# Rocketry_circuit.net
KiCad netlist of a schematic drawn in EAGLE
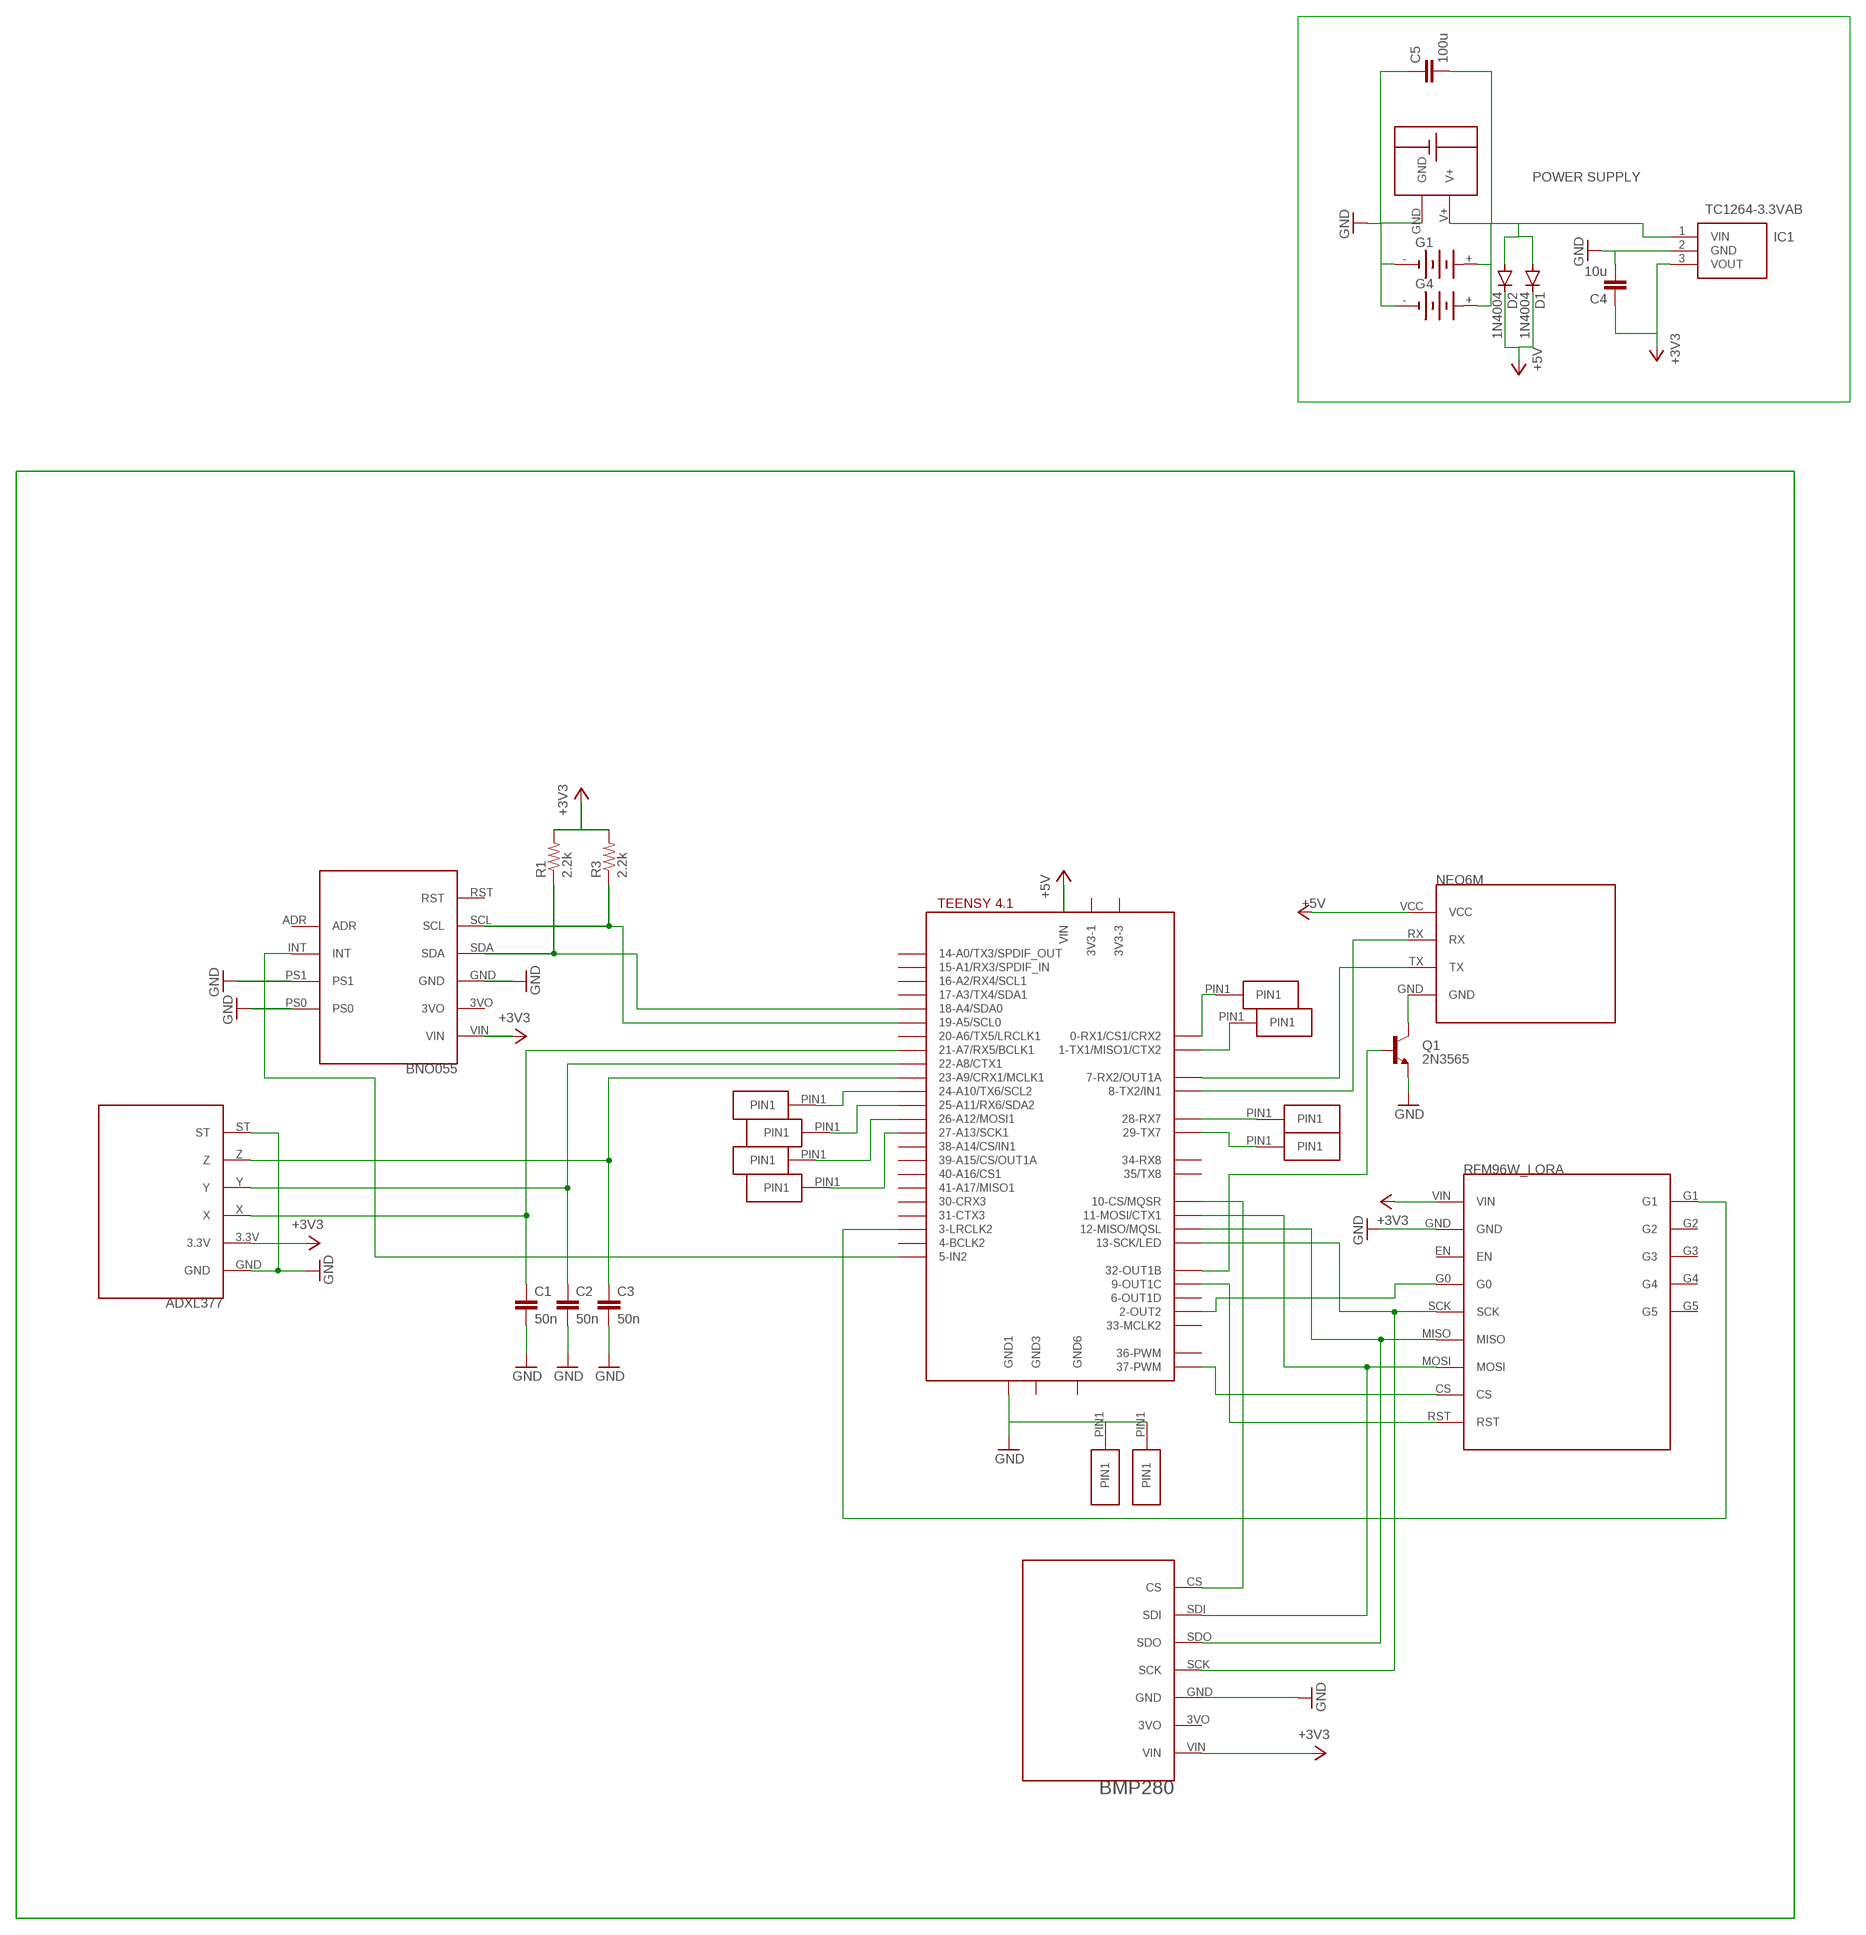
[diagram p0: schematic, sheet 1]

(export (version "E")
  (design (tool "Eeschema 10.0.6"))
  (components
    (comp (ref "BRKOUT1")
      (value "BNO055")
      (footprint "eagle-import:BNO055")
      (libsource (lib "eagle-import") (part "BNO055"))
    )
    (comp (ref "C1")
      (value "50n")
      (footprint "eagle-import:C2.5-3")
      (libsource (lib "eagle-import") (part "C2,5-3"))
    )
    (comp (ref "C2")
      (value "50n")
      (footprint "eagle-import:C2.5-3")
      (libsource (lib "eagle-import") (part "C2,5-3"))
    )
    (comp (ref "C3")
      (value "50n")
      (footprint "eagle-import:C2.5-3")
      (libsource (lib "eagle-import") (part "C2,5-3"))
    )
    (comp (ref "C4")
      (value "10u")
      (footprint "eagle-import:C2.5-3")
      (libsource (lib "eagle-import") (part "C2,5-3"))
    )
    (comp (ref "C5")
      (value "100u")
      (footprint "eagle-import:C2.5-3")
      (libsource (lib "eagle-import") (part "C2,5-3"))
    )
    (comp (ref "D1")
      (value "1N4004")
      (footprint "eagle-import:DO41-10")
      (libsource (lib "eagle-import") (part "1N4004"))
    )
    (comp (ref "D2")
      (value "1N4004")
      (footprint "eagle-import:DO41-10")
      (libsource (lib "eagle-import") (part "1N4004"))
    )
    (comp (ref "G1")
      (value "3V11R")
      (footprint "eagle-import:3V11R")
      (libsource (lib "eagle-import") (part "3V11R"))
    )
    (comp (ref "G4")
      (value "3V11R")
      (footprint "eagle-import:3V11R")
      (libsource (lib "eagle-import") (part "3V11R"))
    )
    (comp (ref "IC1")
      (value "TC1264-3.3VAB")
      (footprint "eagle-import:TO254P483X988X2222-3P")
      (fields (field (name "MOUSER_PART_NUMBER") "579-TC1264-3.3VAB"))
      (libsource (lib "eagle-import") (part "TC1264-3.3VAB"))
    )
    (comp (ref "Q1")
      (value "2N3565")
      (footprint "eagle-import:TO92")
      (libsource (lib "eagle-import") (part "2N3565"))
    )
    (comp (ref "R1")
      (value "2.2k")
      (footprint "eagle-import:0207_5V")
      (libsource (lib "eagle-import") (part "R-US_0207/5V"))
    )
    (comp (ref "R3")
      (value "2.2k")
      (footprint "eagle-import:0207_5V")
      (libsource (lib "eagle-import") (part "R-US_0207/5V"))
    )
    (comp (ref "U$1")
      (value "TEENSY41")
      (footprint "eagle-import:TEENSY41")
      (libsource (lib "eagle-import") (part "TEENSY41"))
    )
    (comp (ref "U$2")
      (value "BMP280")
      (footprint "eagle-import:BMP280")
      (libsource (lib "eagle-import") (part "BMP280"))
    )
    (comp (ref "U$3")
      (value "ADXL377")
      (footprint "eagle-import:ADXL377")
      (libsource (lib "eagle-import") (part "ADXL377"))
    )
    (comp (ref "U$4")
      (value "NEO6M")
      (footprint "eagle-import:NEO6M")
      (libsource (lib "eagle-import") (part "NEO6M"))
    )
    (comp (ref "U$5")
      (value "RFM96W")
      (footprint "eagle-import:RFM96W")
      (libsource (lib "eagle-import") (part "RFM96W"))
    )
    (comp (ref "U$6")
      (value "1PINOUT")
      (footprint "eagle-import:1PINOUT")
      (libsource (lib "eagle-import") (part "1PINOUT"))
    )
    (comp (ref "U$7")
      (value "1PINOUT")
      (footprint "eagle-import:1PINOUT")
      (libsource (lib "eagle-import") (part "1PINOUT"))
    )
    (comp (ref "U$8")
      (value "1PINOUT")
      (footprint "eagle-import:1PINOUT")
      (libsource (lib "eagle-import") (part "1PINOUT"))
    )
    (comp (ref "U$9")
      (value "1PINOUT")
      (footprint "eagle-import:1PINOUT")
      (libsource (lib "eagle-import") (part "1PINOUT"))
    )
    (comp (ref "U$10")
      (value "1PINOUT")
      (footprint "eagle-import:1PINOUT")
      (libsource (lib "eagle-import") (part "1PINOUT"))
    )
    (comp (ref "U$11")
      (value "1PINOUT")
      (footprint "eagle-import:1PINOUT")
      (libsource (lib "eagle-import") (part "1PINOUT"))
    )
    (comp (ref "U$12")
      (value "SMALL_SCREW_TERMINAL")
      (footprint "eagle-import:SMALL_SCREW_TERMINAL")
      (libsource (lib "eagle-import") (part "SMALL_SCREW_TERMINAL"))
    )
    (comp (ref "U$13")
      (value "1PINOUT")
      (footprint "eagle-import:1PINOUT")
      (libsource (lib "eagle-import") (part "1PINOUT"))
    )
    (comp (ref "U$14")
      (value "1PINOUT")
      (footprint "eagle-import:1PINOUT")
      (libsource (lib "eagle-import") (part "1PINOUT"))
    )
    (comp (ref "U$15")
      (value "1PINOUT")
      (footprint "eagle-import:1PINOUT")
      (libsource (lib "eagle-import") (part "1PINOUT"))
    )
    (comp (ref "U$16")
      (value "1PINOUT")
      (footprint "eagle-import:1PINOUT")
      (libsource (lib "eagle-import") (part "1PINOUT"))
    )
  )
  (nets
    (net (code "1") (name "+3V3") (class "Default")
      (node (ref "BRKOUT1") (pin "VIN") (pinfunction "VIN_VIN") (pintype "power_in"))
      (node (ref "C4") (pin "1") (pinfunction "1_1") (pintype "passive"))
      (node (ref "IC1") (pin "3") (pinfunction "VOUT_3") (pintype "bidirectional"))
      (node (ref "R1") (pin "2") (pinfunction "2_2") (pintype "passive"))
      (node (ref "R3") (pin "2") (pinfunction "2_2") (pintype "passive"))
      (node (ref "U$2") (pin "VIN") (pinfunction "VIN_VIN") (pintype "bidirectional"))
      (node (ref "U$3") (pin "3.3V") (pinfunction "3.3V_3.3V") (pintype "bidirectional"))
      (node (ref "U$5") (pin "VIN") (pinfunction "VIN_VIN") (pintype "bidirectional"))
    )
    (net (code "2") (name "+5V") (class "Default")
      (node (ref "D1") (pin "C") (pinfunction "C_C") (pintype "passive"))
      (node (ref "D2") (pin "C") (pinfunction "C_C") (pintype "passive"))
      (node (ref "U$1") (pin "VIN") (pinfunction "VIN_VIN") (pintype "bidirectional"))
      (node (ref "U$4") (pin "VCC") (pinfunction "VCC_VCC") (pintype "bidirectional"))
    )
    (net (code "3") (name "/3VO") (class "Default")
      (node (ref "BRKOUT1") (pin "3VO") (pinfunction "3VO_3VO") (pintype "power_in"))
    )
    (net (code "4") (name "GND") (class "Default")
      (node (ref "BRKOUT1") (pin "GND") (pinfunction "GND_GND") (pintype "power_in"))
      (node (ref "BRKOUT1") (pin "PS0") (pinfunction "PS0_PS0") (pintype "bidirectional"))
      (node (ref "BRKOUT1") (pin "PS1") (pinfunction "PS1_PS1") (pintype "bidirectional"))
      (node (ref "C1") (pin "2") (pinfunction "2_2") (pintype "passive"))
      (node (ref "C2") (pin "2") (pinfunction "2_2") (pintype "passive"))
      (node (ref "C3") (pin "2") (pinfunction "2_2") (pintype "passive"))
      (node (ref "C4") (pin "2") (pinfunction "2_2") (pintype "passive"))
      (node (ref "C5") (pin "1") (pinfunction "1_1") (pintype "passive"))
      (node (ref "G1") (pin "-") (pinfunction "-_-") (pintype "passive"))
      (node (ref "G4") (pin "-") (pinfunction "-_-") (pintype "passive"))
      (node (ref "IC1") (pin "2") (pinfunction "GND_2") (pintype "bidirectional"))
      (node (ref "Q1") (pin "3") (pinfunction "E_3") (pintype "passive"))
      (node (ref "U$1") (pin "GND1") (pinfunction "GND1_GND1") (pintype "bidirectional"))
      (node (ref "U$10") (pin "PIN1") (pinfunction "PIN1_PIN1") (pintype "bidirectional"))
      (node (ref "U$11") (pin "PIN1") (pinfunction "PIN1_PIN1") (pintype "bidirectional"))
      (node (ref "U$12") (pin "GND") (pinfunction "GND_GND") (pintype "bidirectional"))
      (node (ref "U$2") (pin "GND") (pinfunction "GND_GND") (pintype "bidirectional"))
      (node (ref "U$3") (pin "GND") (pinfunction "GND_GND") (pintype "bidirectional"))
      (node (ref "U$3") (pin "ST") (pinfunction "ST_ST") (pintype "bidirectional"))
      (node (ref "U$5") (pin "GND") (pinfunction "GND_GND") (pintype "bidirectional"))
    )
    (net (code "5") (name "Net-(BRKOUT1-PadINT)") (class "Default")
      (node (ref "BRKOUT1") (pin "INT") (pinfunction "INT_INT") (pintype "bidirectional"))
      (node (ref "U$1") (pin "5-IN2") (pinfunction "5-IN2_5-IN2") (pintype "bidirectional"))
    )
    (net (code "6") (name "Net-(BRKOUT1-PadSCL)") (class "Default")
      (node (ref "BRKOUT1") (pin "SCL") (pinfunction "SCL_SCL") (pintype "bidirectional"))
      (node (ref "R3") (pin "1") (pinfunction "1_1") (pintype "passive"))
      (node (ref "U$1") (pin "19-A5/SCL0") (pinfunction "19-A5/SCL0_19-A5/SCL0") (pintype "bidirectional"))
    )
    (net (code "7") (name "Net-(BRKOUT1-PadSDA)") (class "Default")
      (node (ref "BRKOUT1") (pin "SDA") (pinfunction "SDA_SDA") (pintype "bidirectional"))
      (node (ref "R1") (pin "1") (pinfunction "1_1") (pintype "passive"))
      (node (ref "U$1") (pin "18-A4/SDA0") (pinfunction "18-A4/SDA0_18-A4/SDA0") (pintype "bidirectional"))
    )
    (net (code "8") (name "Net-(C1-Pad1)") (class "Default")
      (node (ref "C1") (pin "1") (pinfunction "1_1") (pintype "passive"))
      (node (ref "U$1") (pin "21-A7/RX5/BCLK1") (pinfunction "21-A7/RX5/BCLK1_21-A7/RX5/BCLK1") (pintype "bidirectional"))
      (node (ref "U$3") (pin "X") (pinfunction "X_X") (pintype "bidirectional"))
    )
    (net (code "9") (name "Net-(C2-Pad1)") (class "Default")
      (node (ref "C2") (pin "1") (pinfunction "1_1") (pintype "passive"))
      (node (ref "U$1") (pin "22-A8/CTX1") (pinfunction "22-A8/CTX1_22-A8/CTX1") (pintype "bidirectional"))
      (node (ref "U$3") (pin "Y") (pinfunction "Y_Y") (pintype "bidirectional"))
    )
    (net (code "10") (name "Net-(C3-Pad1)") (class "Default")
      (node (ref "C3") (pin "1") (pinfunction "1_1") (pintype "passive"))
      (node (ref "U$1") (pin "23-A9/CRX1/MCLK1") (pinfunction "23-A9/CRX1/MCLK1_23-A9/CRX1/MCLK1") (pintype "bidirectional"))
      (node (ref "U$3") (pin "Z") (pinfunction "Z_Z") (pintype "bidirectional"))
    )
    (net (code "11") (name "Net-(IC1-VIN)") (class "Default")
      (node (ref "C5") (pin "2") (pinfunction "2_2") (pintype "passive"))
      (node (ref "D1") (pin "A") (pinfunction "A_A") (pintype "passive"))
      (node (ref "D2") (pin "A") (pinfunction "A_A") (pintype "passive"))
      (node (ref "G1") (pin "+") (pinfunction "+_+") (pintype "passive"))
      (node (ref "G4") (pin "+") (pinfunction "+_+") (pintype "passive"))
      (node (ref "IC1") (pin "1") (pinfunction "VIN_1") (pintype "bidirectional"))
      (node (ref "U$12") (pin "V+") (pinfunction "V+_V+") (pintype "bidirectional"))
    )
    (net (code "12") (name "Net-(Q1-B)") (class "Default")
      (node (ref "Q1") (pin "2") (pinfunction "B_2") (pintype "passive"))
      (node (ref "U$1") (pin "32-OUT1B") (pinfunction "32-OUT1B_32-OUT1B") (pintype "bidirectional"))
    )
    (net (code "13") (name "Net-(Q1-C)") (class "Default")
      (node (ref "Q1") (pin "1") (pinfunction "C_1") (pintype "passive"))
      (node (ref "U$4") (pin "GND") (pinfunction "GND_GND") (pintype "bidirectional"))
    )
    (net (code "14") (name "Net-(U$1-8-TX2{slash}IN1)") (class "Default")
      (node (ref "U$1") (pin "8-TX2/IN2") (pinfunction "8-TX2/IN1_8-TX2/IN2") (pintype "bidirectional"))
      (node (ref "U$4") (pin "RX") (pinfunction "RX_RX") (pintype "bidirectional"))
    )
    (net (code "15") (name "Net-(U$1-10-CS{slash}MQSR)") (class "Default")
      (node (ref "U$1") (pin "10-CS\\MQSR") (pinfunction "10-CS/MQSR_10-CS\\MQSR") (pintype "bidirectional"))
      (node (ref "U$2") (pin "CS") (pinfunction "CS_CS") (pintype "bidirectional"))
    )
    (net (code "16") (name "Net-(U$1-Pad0-RX1{slash}CS1{slash}CRX2)") (class "Default")
      (node (ref "U$1") (pin "0-RX1/CS1/CRX2") (pinfunction "0-RX1/CS1/CRX2_0-RX1/CS1/CRX2") (pintype "bidirectional"))
      (node (ref "U$15") (pin "PIN1") (pinfunction "PIN1_PIN1") (pintype "bidirectional"))
    )
    (net (code "17") (name "Net-(U$1-Pad1-TX1{slash}MISO1{slash}CTX2)") (class "Default")
      (node (ref "U$1") (pin "1-TX1/MISO1/CTX2") (pinfunction "1-TX1/MISO1/CTX2_1-TX1/MISO1/CTX2") (pintype "bidirectional"))
      (node (ref "U$16") (pin "PIN1") (pinfunction "PIN1_PIN1") (pintype "bidirectional"))
    )
    (net (code "18") (name "Net-(U$1-Pad2-OUT2)") (class "Default")
      (node (ref "U$1") (pin "2-OUT2") (pinfunction "2-OUT2_2-OUT2") (pintype "bidirectional"))
      (node (ref "U$5") (pin "G0") (pinfunction "G0_G0") (pintype "bidirectional"))
    )
    (net (code "19") (name "Net-(U$1-Pad3-LRCLK2)") (class "Default")
      (node (ref "U$1") (pin "3-LRCLK2") (pinfunction "3-LRCLK2_3-LRCLK2") (pintype "bidirectional"))
      (node (ref "U$5") (pin "G1") (pinfunction "G1_G1") (pintype "bidirectional"))
    )
    (net (code "20") (name "Net-(U$1-Pad7-RX2{slash}OUT1A)") (class "Default")
      (node (ref "U$1") (pin "7-RX2/OUT1A") (pinfunction "7-RX2/OUT1A_7-RX2/OUT1A") (pintype "bidirectional"))
      (node (ref "U$4") (pin "TX") (pinfunction "TX_TX") (pintype "bidirectional"))
    )
    (net (code "21") (name "Net-(U$1-Pad9-OUT1C)") (class "Default")
      (node (ref "U$1") (pin "9-OUT1C") (pinfunction "9-OUT1C_9-OUT1C") (pintype "bidirectional"))
      (node (ref "U$5") (pin "RST") (pinfunction "RST_RST") (pintype "bidirectional"))
    )
    (net (code "22") (name "Net-(U$1-Pad11-MOSI{slash}CTX1)") (class "Default")
      (node (ref "U$1") (pin "11-MOSI/CTX1") (pinfunction "11-MOSI/CTX1_11-MOSI/CTX1") (pintype "bidirectional"))
      (node (ref "U$2") (pin "SDI") (pinfunction "SDI_SDI") (pintype "bidirectional"))
      (node (ref "U$5") (pin "MOSI") (pinfunction "MOSI_MOSI") (pintype "bidirectional"))
    )
    (net (code "23") (name "Net-(U$1-Pad12-MISO{slash}MQSL)") (class "Default")
      (node (ref "U$1") (pin "12-MISO/MQSL") (pinfunction "12-MISO/MQSL_12-MISO/MQSL") (pintype "bidirectional"))
      (node (ref "U$2") (pin "SDO") (pinfunction "SDO_SDO") (pintype "bidirectional"))
      (node (ref "U$5") (pin "MISO") (pinfunction "MISO_MISO") (pintype "bidirectional"))
    )
    (net (code "24") (name "Net-(U$1-Pad13-SCK{slash}LED)") (class "Default")
      (node (ref "U$1") (pin "13-SCK/LED") (pinfunction "13-SCK/LED_13-SCK/LED") (pintype "bidirectional"))
      (node (ref "U$2") (pin "SCK") (pinfunction "SCK_SCK") (pintype "bidirectional"))
      (node (ref "U$5") (pin "SCK") (pinfunction "SCK_SCK") (pintype "bidirectional"))
    )
    (net (code "25") (name "Net-(U$1-Pad24-A10{slash}TX6{slash}SCL2)") (class "Default")
      (node (ref "U$1") (pin "24-A10/TX6/SCL2") (pinfunction "24-A10/TX6/SCL2_24-A10/TX6/SCL2") (pintype "bidirectional"))
      (node (ref "U$9") (pin "PIN1") (pinfunction "PIN1_PIN1") (pintype "bidirectional"))
    )
    (net (code "26") (name "Net-(U$1-Pad25-A11{slash}RX6{slash}SDA2)") (class "Default")
      (node (ref "U$1") (pin "25-A11/RX6/SDA2") (pinfunction "25-A11/RX6/SDA2_25-A11/RX6/SDA2") (pintype "bidirectional"))
      (node (ref "U$7") (pin "PIN1") (pinfunction "PIN1_PIN1") (pintype "bidirectional"))
    )
    (net (code "27") (name "Net-(U$1-Pad26-A12{slash}MOSI1)") (class "Default")
      (node (ref "U$1") (pin "26-A12/MOSI1") (pinfunction "26-A12/MOSI1_26-A12/MOSI1") (pintype "bidirectional"))
      (node (ref "U$13") (pin "PIN1") (pinfunction "PIN1_PIN1") (pintype "bidirectional"))
    )
    (net (code "28") (name "Net-(U$1-Pad27-A13{slash}SCK1)") (class "Default")
      (node (ref "U$1") (pin "27-A13/SCK1") (pinfunction "27-A13/SCK1_27-A13/SCK1") (pintype "bidirectional"))
      (node (ref "U$14") (pin "PIN1") (pinfunction "PIN1_PIN1") (pintype "bidirectional"))
    )
    (net (code "29") (name "Net-(U$1-Pad28-RX7)") (class "Default")
      (node (ref "U$1") (pin "28-RX7") (pinfunction "28-RX7_28-RX7") (pintype "bidirectional"))
      (node (ref "U$6") (pin "PIN1") (pinfunction "PIN1_PIN1") (pintype "bidirectional"))
    )
    (net (code "30") (name "Net-(U$1-Pad29-TX7)") (class "Default")
      (node (ref "U$1") (pin "29-TX7") (pinfunction "29-TX7_29-TX7") (pintype "bidirectional"))
      (node (ref "U$8") (pin "PIN1") (pinfunction "PIN1_PIN1") (pintype "bidirectional"))
    )
    (net (code "31") (name "Net-(U$1-Pad37-PWM)") (class "Default")
      (node (ref "U$1") (pin "37-PWM") (pinfunction "37-PWM_37-PWM") (pintype "bidirectional"))
      (node (ref "U$5") (pin "CS") (pinfunction "CS_CS") (pintype "bidirectional"))
    )
    (net (code "32") (name "unconnected-(BRKOUT1-PadADR)") (class "Default")
      (node (ref "BRKOUT1") (pin "ADR") (pinfunction "ADR_ADR") (pintype "bidirectional"))
    )
    (net (code "33") (name "unconnected-(BRKOUT1-PadRST)") (class "Default")
      (node (ref "BRKOUT1") (pin "RST") (pinfunction "RST_RST") (pintype "bidirectional"))
    )
    (net (code "34") (name "unconnected-(U$1-35{slash}TX8-Pad35-TX8)") (class "Default")
      (node (ref "U$1") (pin "35-TX8") (pinfunction "35/TX8_35-TX8") (pintype "bidirectional"))
    )
    (net (code "35") (name "unconnected-(U$1-Pad3V3-1)") (class "Default")
      (node (ref "U$1") (pin "3V3-1") (pinfunction "3V3-1_3V3-1") (pintype "bidirectional"))
    )
    (net (code "36") (name "unconnected-(U$1-Pad3V3-3)") (class "Default")
      (node (ref "U$1") (pin "3V3-3") (pinfunction "3V3-3_3V3-3") (pintype "bidirectional"))
    )
    (net (code "37") (name "unconnected-(U$1-Pad4-BCLK2)") (class "Default")
      (node (ref "U$1") (pin "4-BCLK2") (pinfunction "4-BCLK2_4-BCLK2") (pintype "bidirectional"))
    )
    (net (code "38") (name "unconnected-(U$1-Pad6-OUT1D)") (class "Default")
      (node (ref "U$1") (pin "6-OUT1D") (pinfunction "6-OUT1D_6-OUT1D") (pintype "bidirectional"))
    )
    (net (code "39") (name "unconnected-(U$1-Pad14-A0{slash}TX3{slash}SPDIF_OUT)") (class "Default")
      (node (ref "U$1") (pin "14-A0/TX3/SPDIF_OUT") (pinfunction "14-A0/TX3/SPDIF_OUT_14-A0/TX3/SPDIF_OUT") (pintype "bidirectional"))
    )
    (net (code "40") (name "unconnected-(U$1-Pad15-A1{slash}RX3{slash}SPDIF_IN)") (class "Default")
      (node (ref "U$1") (pin "15-A1/RX3/SPDIF_IN") (pinfunction "15-A1/RX3/SPDIF_IN_15-A1/RX3/SPDIF_IN") (pintype "bidirectional"))
    )
    (net (code "41") (name "unconnected-(U$1-Pad16-A2{slash}RX4{slash}SCL1)") (class "Default")
      (node (ref "U$1") (pin "16-A2/RX4/SCL1") (pinfunction "16-A2/RX4/SCL1_16-A2/RX4/SCL1") (pintype "bidirectional"))
    )
    (net (code "42") (name "unconnected-(U$1-Pad17-A3{slash}TX4{slash}SDA1)") (class "Default")
      (node (ref "U$1") (pin "17-A3/TX4/SDA1") (pinfunction "17-A3/TX4/SDA1_17-A3/TX4/SDA1") (pintype "bidirectional"))
    )
    (net (code "43") (name "unconnected-(U$1-Pad20-A6{slash}TX5{slash}LRCLK1)") (class "Default")
      (node (ref "U$1") (pin "20-A6/TX5/LRCLK1") (pinfunction "20-A6/TX5/LRCLK1_20-A6/TX5/LRCLK1") (pintype "bidirectional"))
    )
    (net (code "44") (name "unconnected-(U$1-Pad30-CRX3)") (class "Default")
      (node (ref "U$1") (pin "30-CRX3") (pinfunction "30-CRX3_30-CRX3") (pintype "bidirectional"))
    )
    (net (code "45") (name "unconnected-(U$1-Pad31-CTX3)") (class "Default")
      (node (ref "U$1") (pin "31-CTX3") (pinfunction "31-CTX3_31-CTX3") (pintype "bidirectional"))
    )
    (net (code "46") (name "unconnected-(U$1-Pad33-MCLK2)") (class "Default")
      (node (ref "U$1") (pin "33-MCLK2") (pinfunction "33-MCLK2_33-MCLK2") (pintype "bidirectional"))
    )
    (net (code "47") (name "unconnected-(U$1-Pad34-RX8)") (class "Default")
      (node (ref "U$1") (pin "34-RX8") (pinfunction "34-RX8_34-RX8") (pintype "bidirectional"))
    )
    (net (code "48") (name "unconnected-(U$1-Pad36-PWM)") (class "Default")
      (node (ref "U$1") (pin "36-PWM") (pinfunction "36-PWM_36-PWM") (pintype "bidirectional"))
    )
    (net (code "49") (name "unconnected-(U$1-Pad38-A14{slash}CS{slash}IN1)") (class "Default")
      (node (ref "U$1") (pin "38-A14/CS/IN1") (pinfunction "38-A14/CS/IN1_38-A14/CS/IN1") (pintype "bidirectional"))
    )
    (net (code "50") (name "unconnected-(U$1-Pad39-A15{slash}CS{slash}OUT1A)") (class "Default")
      (node (ref "U$1") (pin "39-A15/CS/OUT1A") (pinfunction "39-A15/CS/OUT1A_39-A15/CS/OUT1A") (pintype "bidirectional"))
    )
    (net (code "51") (name "unconnected-(U$1-Pad40-A16{slash}CS1)") (class "Default")
      (node (ref "U$1") (pin "40-A16/CS1") (pinfunction "40-A16/CS1_40-A16/CS1") (pintype "bidirectional"))
    )
    (net (code "52") (name "unconnected-(U$1-Pad41-A17{slash}MISO1)") (class "Default")
      (node (ref "U$1") (pin "41-A17/MISO1") (pinfunction "41-A17/MISO1_41-A17/MISO1") (pintype "bidirectional"))
    )
    (net (code "53") (name "unconnected-(U$1-PadGND3)") (class "Default")
      (node (ref "U$1") (pin "GND3") (pinfunction "GND3_GND3") (pintype "bidirectional"))
    )
    (net (code "54") (name "unconnected-(U$1-PadGND6)") (class "Default")
      (node (ref "U$1") (pin "GND6") (pinfunction "GND6_GND6") (pintype "bidirectional"))
    )
    (net (code "55") (name "unconnected-(U$2-Pad3VO)") (class "Default")
      (node (ref "U$2") (pin "3VO") (pinfunction "3VO_3VO") (pintype "bidirectional"))
    )
    (net (code "56") (name "unconnected-(U$5-PadEN)") (class "Default")
      (node (ref "U$5") (pin "EN") (pinfunction "EN_EN") (pintype "bidirectional"))
    )
    (net (code "57") (name "unconnected-(U$5-PadG2)") (class "Default")
      (node (ref "U$5") (pin "G2") (pinfunction "G2_G2") (pintype "bidirectional"))
    )
    (net (code "58") (name "unconnected-(U$5-PadG3)") (class "Default")
      (node (ref "U$5") (pin "G3") (pinfunction "G3_G3") (pintype "bidirectional"))
    )
    (net (code "59") (name "unconnected-(U$5-PadG4)") (class "Default")
      (node (ref "U$5") (pin "G4") (pinfunction "G4_G4") (pintype "bidirectional"))
    )
    (net (code "60") (name "unconnected-(U$5-PadG5)") (class "Default")
      (node (ref "U$5") (pin "G5") (pinfunction "G5_G5") (pintype "bidirectional"))
    )
  )
)
